# SCH_Business-card-no-mcu_2025-04-14.net
KiCad netlist of a schematic drawn in EasyEDA
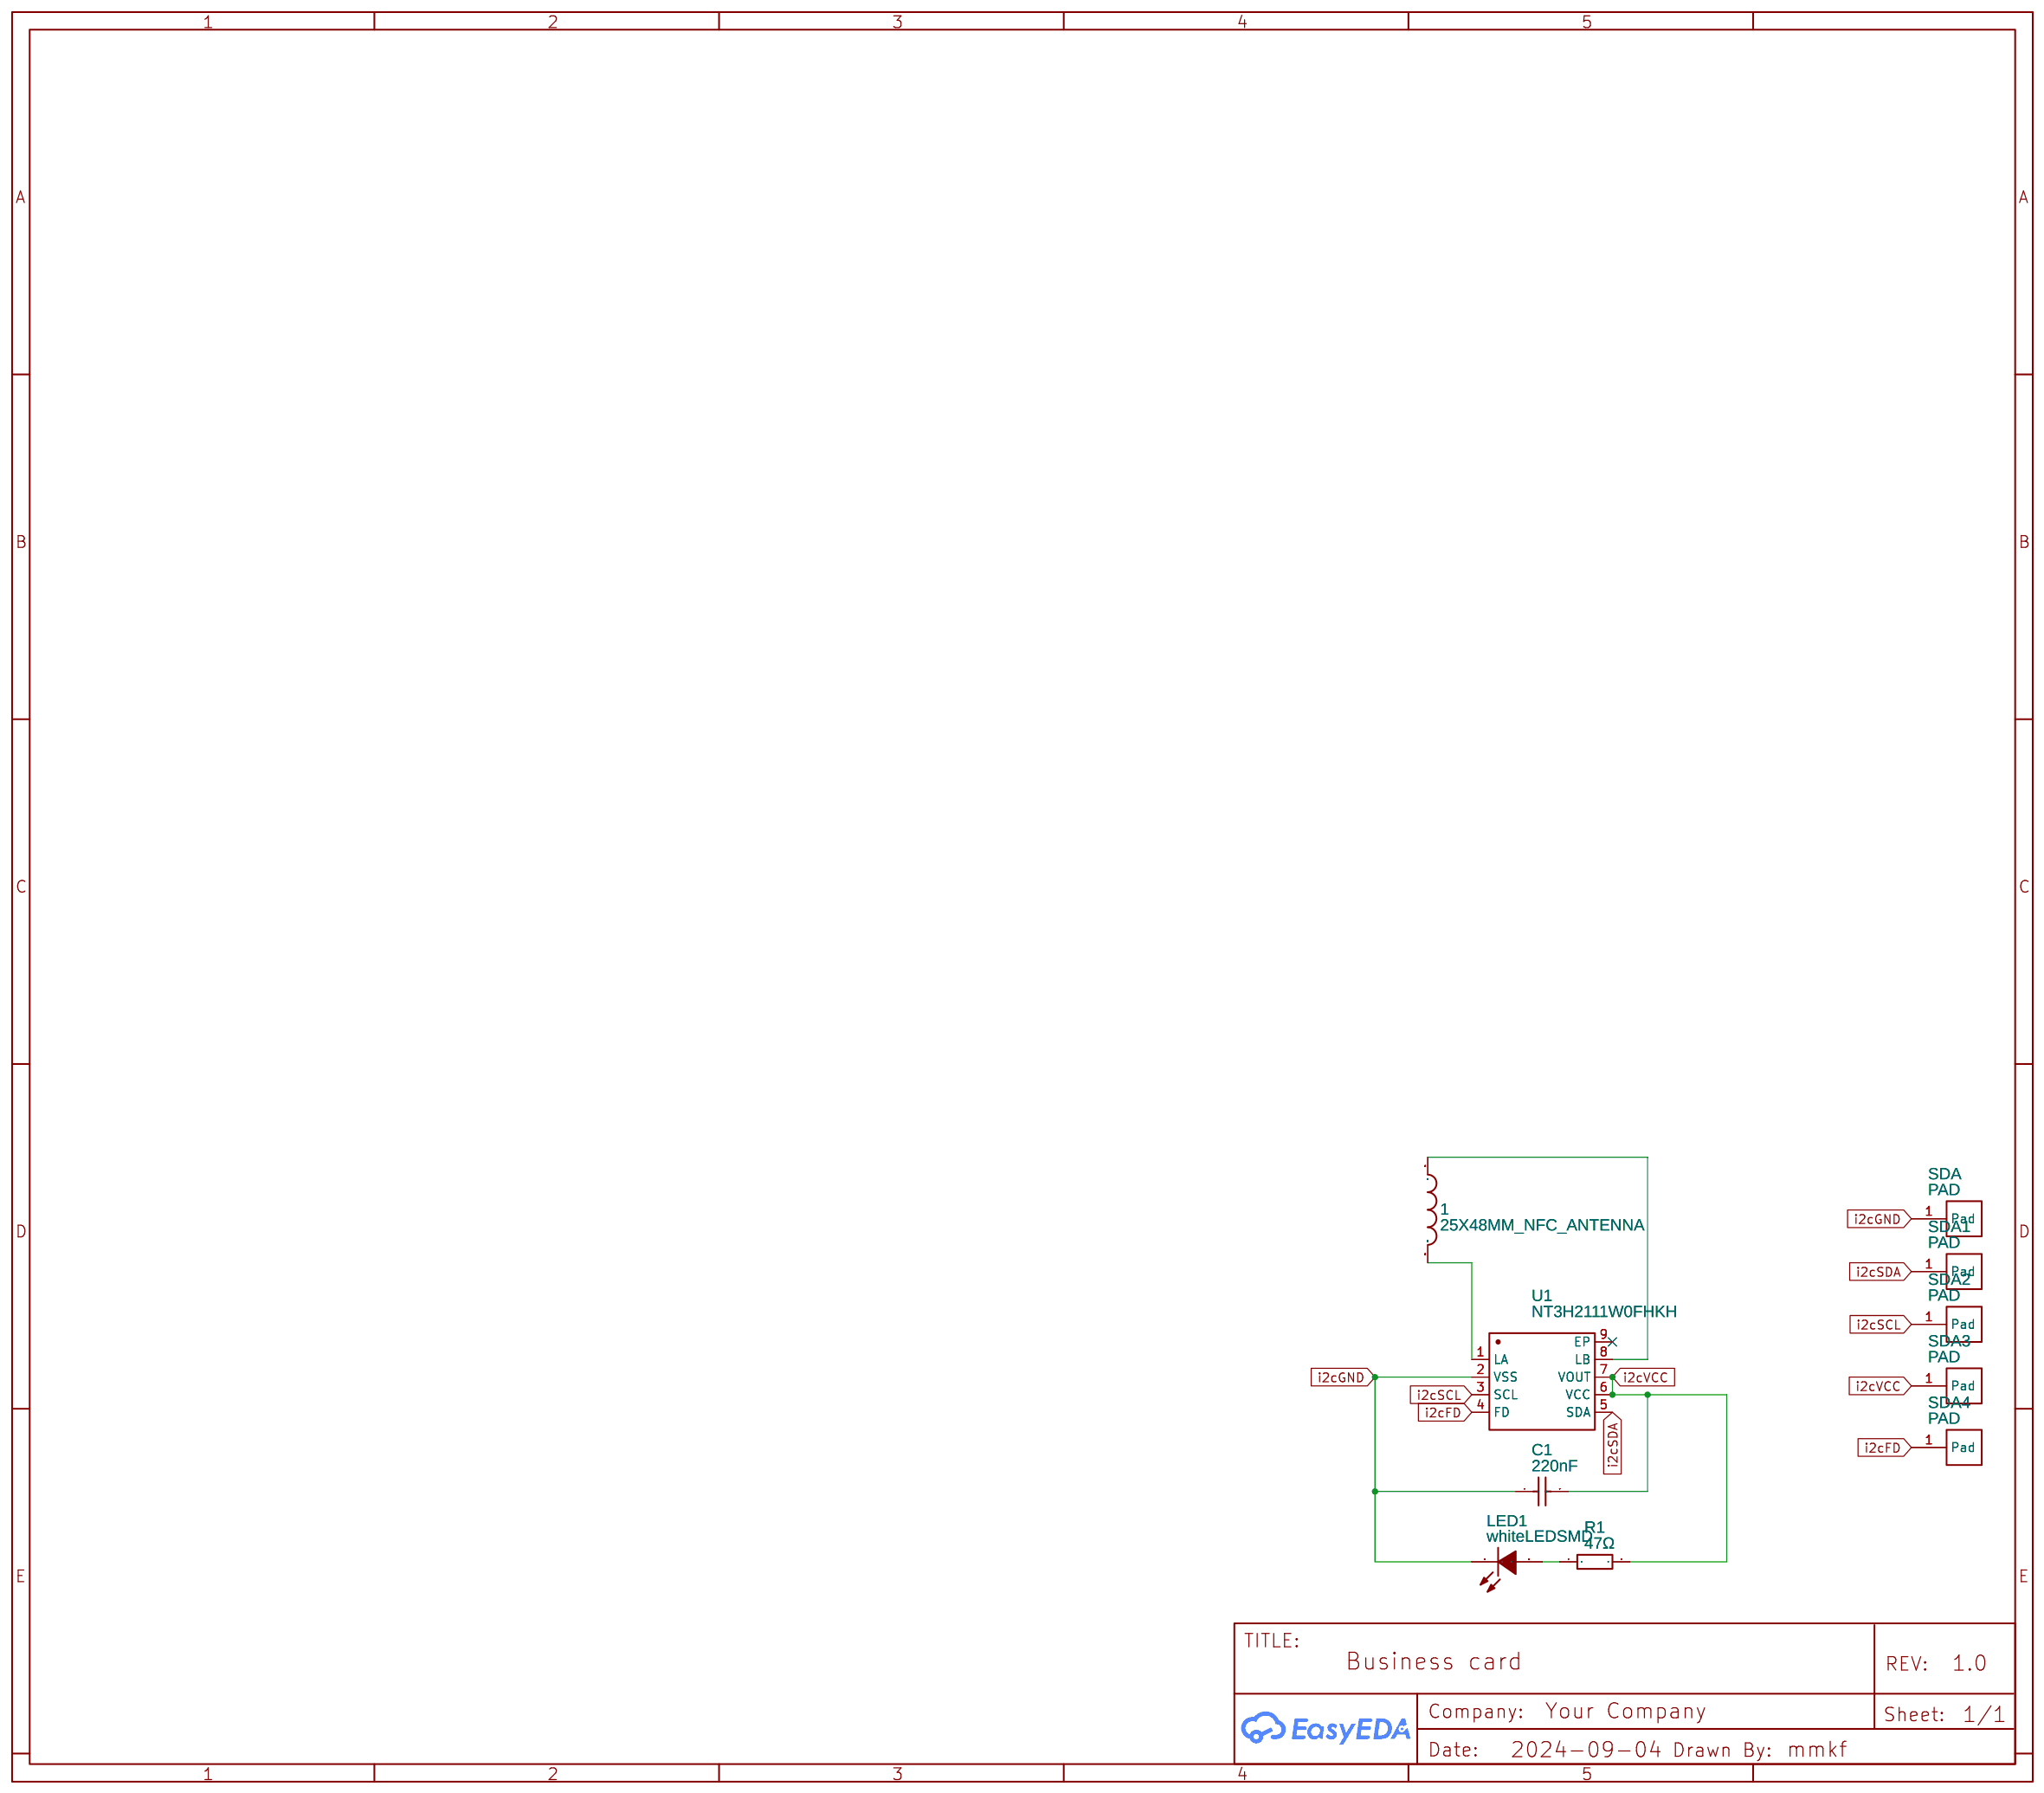
[diagram p0: schematic sheet]

(export (version "E")
  (design (tool "Eeschema 10.0.6"))
  (components
    (comp (ref "1") (value "25X48MM_NFC_ANTENNA") (libsource (lib "") (part "25X48MM_NFC_ANTENNA")))
    (comp (ref "C1")
      (value "220nF")
      (fields
        (field (name "Manufacturer Part") "CL10B224KA8NNNC")
        (field (name "Manufacturer") "SAMSUNG(三星)")
      )
      (libsource (lib "") (part "CL10B224KA8NNNC"))
    )
    (comp (ref "LED1")
      (value "whiteLEDSMD")
      (fields (field (name "Manufacturer Part") "KT-0805W") (field (name "Manufacturer") "KENTO"))
      (libsource (lib "") (part "whiteLEDSMD"))
    )
    (comp (ref "R1")
      (value "47Ω")
      (fields
        (field (name "Manufacturer Part") "0603WAF470JT5E")
        (field (name "Manufacturer") "UNI-ROYAL(厚声)")
      )
      (libsource (lib "") (part "0603WAF470JT5E"))
    )
    (comp (ref "SDA") (value "PAD") (libsource (lib "") (part "PAD")))
    (comp (ref "SDA1") (value "PAD") (libsource (lib "") (part "PAD")))
    (comp (ref "SDA2") (value "PAD") (libsource (lib "") (part "PAD")))
    (comp (ref "SDA3") (value "PAD") (libsource (lib "") (part "PAD")))
    (comp (ref "SDA4") (value "PAD") (libsource (lib "") (part "PAD")))
    (comp (ref "U1")
      (value "NT3H2111W0FHKH")
      (fields (field (name "Manufacturer") "NXP(恩智浦)"))
      (libsource (lib "") (part "NT3H2111W0FHKH"))
    )
  )
  (nets
    (net (code "1") (name "Net-(LED1-A)") (class "Default")
      (node (ref "LED1") (pin "1") (pinfunction "A_1") (pintype "unspecified"))
      (node (ref "R1") (pin "1") (pinfunction "1_1") (pintype "input"))
    )
    (net (code "2") (name "Net-(U1-LA)") (class "Default")
      (node (ref "1") (pin "P$2") (pinfunction "P$2_P$2") (pintype "bidirectional"))
      (node (ref "U1") (pin "1") (pinfunction "LA_1") (pintype "unspecified"))
    )
    (net (code "3") (name "Net-(U1-LB)") (class "Default")
      (node (ref "1") (pin "P$1") (pinfunction "P$1_P$1") (pintype "bidirectional"))
      (node (ref "U1") (pin "8") (pinfunction "LB_8") (pintype "unspecified"))
    )
    (net (code "4") (name "i2cFD") (class "Default")
      (node (ref "SDA4") (pin "1") (pinfunction "Pad_1") (pintype "unspecified"))
      (node (ref "U1") (pin "4") (pinfunction "FD_4") (pintype "unspecified"))
    )
    (net (code "5") (name "i2cGND") (class "Default")
      (node (ref "C1") (pin "1") (pinfunction "1_1") (pintype "input"))
      (node (ref "LED1") (pin "2") (pinfunction "K_2") (pintype "unspecified"))
      (node (ref "SDA") (pin "1") (pinfunction "Pad_1") (pintype "unspecified"))
      (node (ref "U1") (pin "2") (pinfunction "VSS_2") (pintype "unspecified"))
    )
    (net (code "6") (name "i2cSCL") (class "Default")
      (node (ref "SDA2") (pin "1") (pinfunction "Pad_1") (pintype "unspecified"))
      (node (ref "U1") (pin "3") (pinfunction "SCL_3") (pintype "unspecified"))
    )
    (net (code "7") (name "i2cSDA") (class "Default")
      (node (ref "SDA1") (pin "1") (pinfunction "Pad_1") (pintype "unspecified"))
      (node (ref "U1") (pin "5") (pinfunction "SDA_5") (pintype "unspecified"))
    )
    (net (code "8") (name "i2cVCC") (class "Default")
      (node (ref "C1") (pin "2") (pinfunction "2_2") (pintype "input"))
      (node (ref "R1") (pin "2") (pinfunction "2_2") (pintype "input"))
      (node (ref "SDA3") (pin "1") (pinfunction "Pad_1") (pintype "unspecified"))
      (node (ref "U1") (pin "6") (pinfunction "VCC_6") (pintype "unspecified"))
      (node (ref "U1") (pin "7") (pinfunction "VOUT_7") (pintype "unspecified"))
    )
    (net (code "9") (name "unconnected-(U1-EP-Pad9)") (class "Default")
      (node (ref "U1") (pin "9") (pinfunction "EP_9") (pintype "unspecified+no_connect"))
    )
  )
)
